# 2-nand-gate-latching-circuit.net
KiCad netlist of a schematic drawn in EAGLE
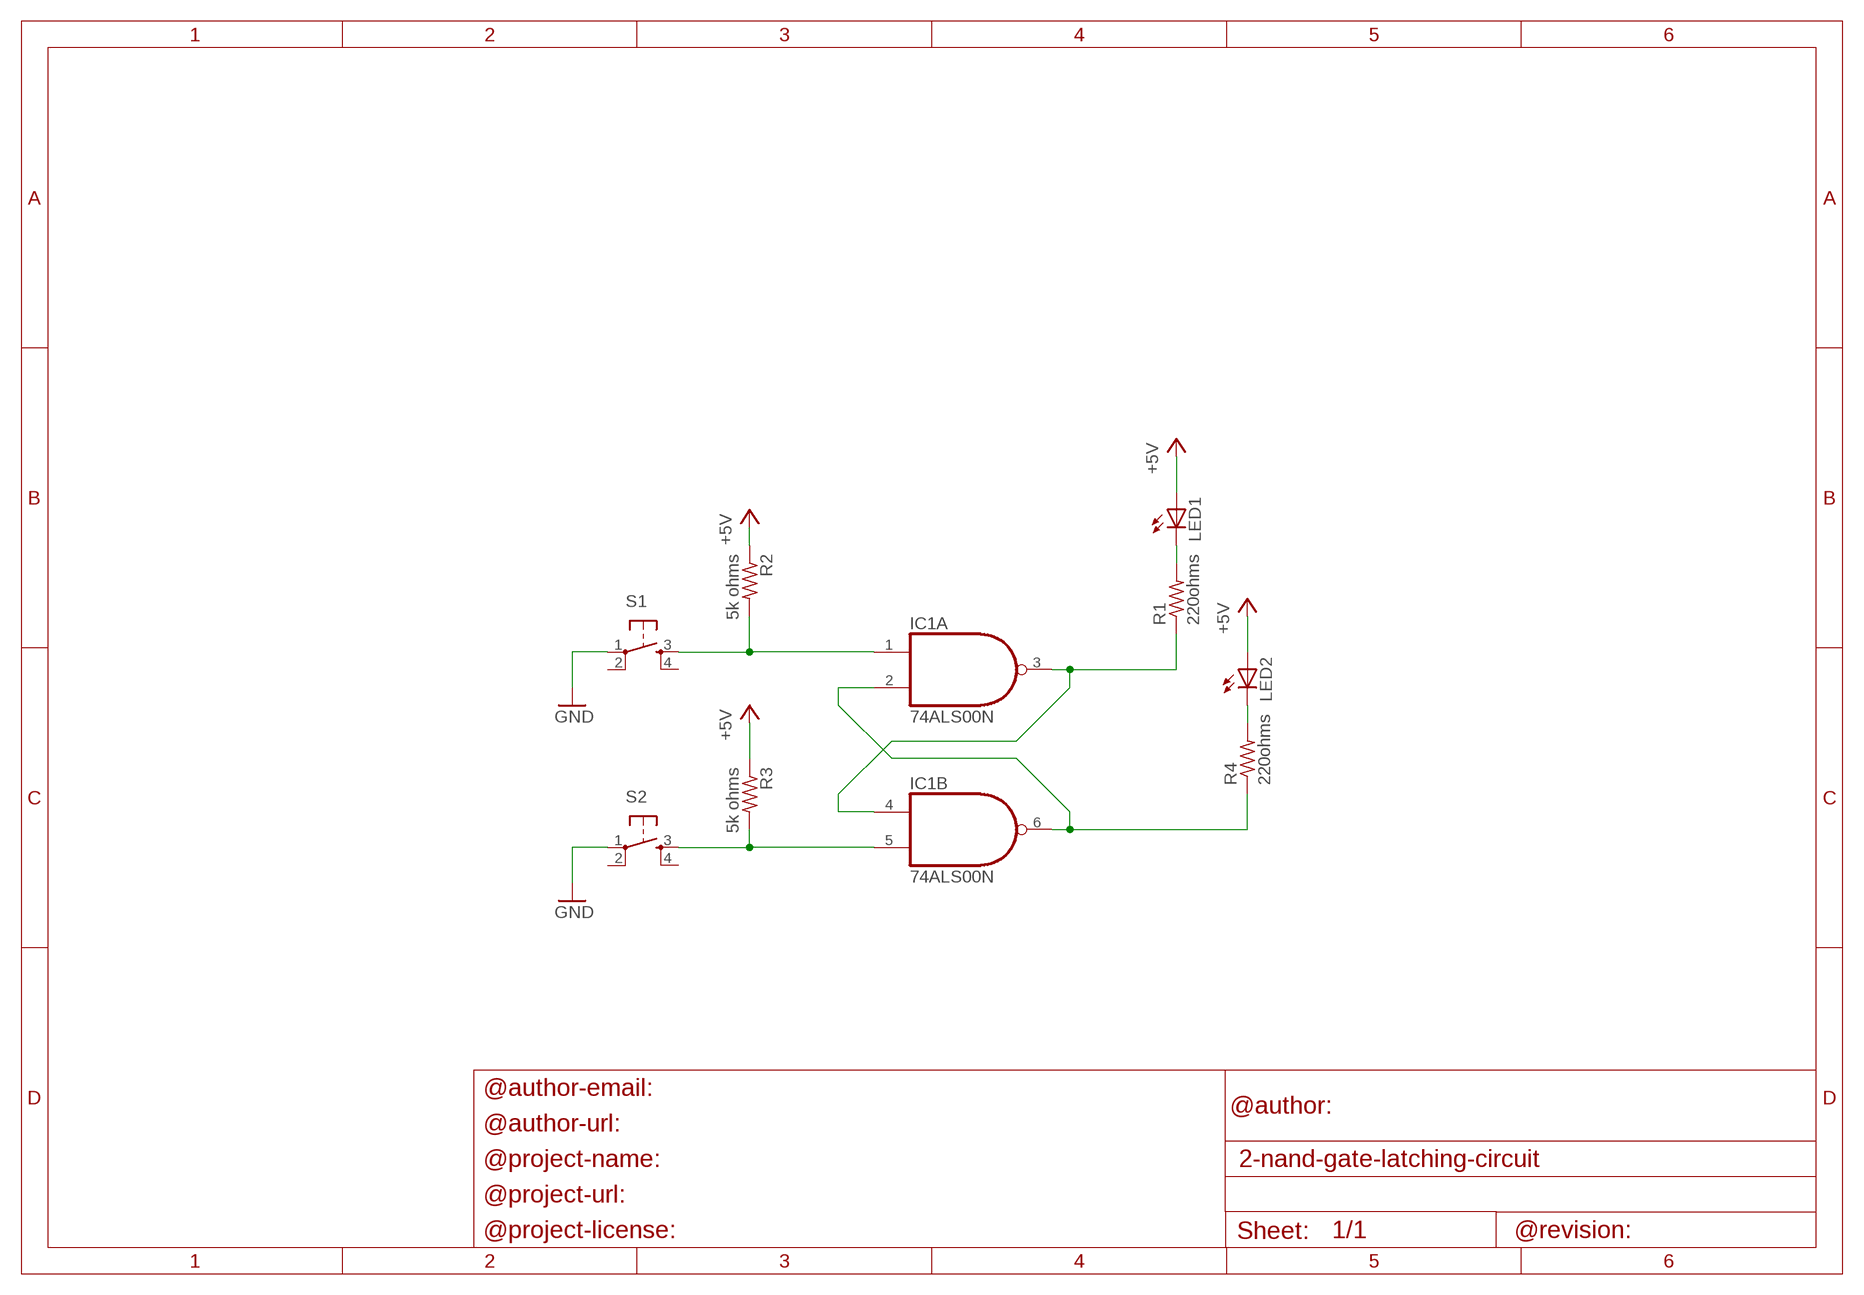
[diagram p0: schematic, sheet 1]

(export (version "E")
  (design (tool "Eeschema 10.0.6"))
  (components
    (comp (ref "IC1")
      (value "74ALS00N")
      (footprint "eagle-import:DIL14")
      (libsource (lib "eagle-import") (part "7400NALS"))
    )
    (comp (ref "LED1")
      (value "LED5MM")
      (footprint "eagle-import:LED5MM")
      (libsource (lib "eagle-import") (part "LED5MM"))
    )
    (comp (ref "LED2")
      (value "LED5MM")
      (footprint "eagle-import:LED5MM")
      (libsource (lib "eagle-import") (part "LED5MM"))
    )
    (comp (ref "R1")
      (value "220ohms")
      (footprint "eagle-import:0204_7")
      (libsource (lib "eagle-import") (part "R-US_0204/7"))
    )
    (comp (ref "R2")
      (value "5k ohms")
      (footprint "eagle-import:0204_7")
      (libsource (lib "eagle-import") (part "R-US_0204/7"))
    )
    (comp (ref "R3")
      (value "5k ohms")
      (footprint "eagle-import:0204_7")
      (libsource (lib "eagle-import") (part "R-US_0204/7"))
    )
    (comp (ref "R4")
      (value "220ohms")
      (footprint "eagle-import:0204_7")
      (libsource (lib "eagle-import") (part "R-US_0204/7"))
    )
    (comp (ref "S1")
      (value "TAC_SWITCHPTH")
      (footprint "eagle-import:TACTILE-PTH")
      (libsource (lib "eagle-import") (part "TAC_SWITCHPTH"))
    )
    (comp (ref "S2")
      (value "TAC_SWITCHPTH")
      (footprint "eagle-import:TACTILE-PTH")
      (libsource (lib "eagle-import") (part "TAC_SWITCHPTH"))
    )
  )
  (nets
    (net (code "1") (name "+5V") (class "Default")
      (node (ref "LED1") (pin "A") (pinfunction "A_A") (pintype "passive"))
      (node (ref "LED2") (pin "A") (pinfunction "A_A") (pintype "passive"))
      (node (ref "R2") (pin "1") (pinfunction "1_1") (pintype "passive"))
      (node (ref "R3") (pin "1") (pinfunction "1_1") (pintype "passive"))
    )
    (net (code "2") (name "GND") (class "Default")
      (node (ref "S1") (pin "1") (pinfunction "1_1") (pintype "passive"))
      (node (ref "S2") (pin "1") (pinfunction "1_1") (pintype "passive"))
    )
    (net (code "3") (name "Net-(IC1A-I0)") (class "Default")
      (node (ref "IC1") (pin "1") (pinfunction "I0_1") (pintype "input"))
      (node (ref "R2") (pin "2") (pinfunction "2_2") (pintype "passive"))
      (node (ref "S1") (pin "3") (pinfunction "3_3") (pintype "passive"))
    )
    (net (code "4") (name "Net-(IC1A-I1)") (class "Default")
      (node (ref "IC1") (pin "2") (pinfunction "I1_2") (pintype "input"))
      (node (ref "IC1") (pin "6") (pinfunction "O_6") (pintype "output"))
      (node (ref "R4") (pin "1") (pinfunction "1_1") (pintype "passive"))
    )
    (net (code "5") (name "Net-(IC1A-O)") (class "Default")
      (node (ref "IC1") (pin "3") (pinfunction "O_3") (pintype "output"))
      (node (ref "IC1") (pin "4") (pinfunction "I0_4") (pintype "input"))
      (node (ref "R1") (pin "1") (pinfunction "1_1") (pintype "passive"))
    )
    (net (code "6") (name "Net-(IC1B-I1)") (class "Default")
      (node (ref "IC1") (pin "5") (pinfunction "I1_5") (pintype "input"))
      (node (ref "R3") (pin "2") (pinfunction "2_2") (pintype "passive"))
      (node (ref "S2") (pin "3") (pinfunction "3_3") (pintype "passive"))
    )
    (net (code "7") (name "Net-(LED1-C)") (class "Default")
      (node (ref "LED1") (pin "K") (pinfunction "C_K") (pintype "passive"))
      (node (ref "R1") (pin "2") (pinfunction "2_2") (pintype "passive"))
    )
    (net (code "8") (name "Net-(LED2-C)") (class "Default")
      (node (ref "LED2") (pin "K") (pinfunction "C_K") (pintype "passive"))
      (node (ref "R4") (pin "2") (pinfunction "2_2") (pintype "passive"))
    )
    (net (code "9") (name "unconnected-(S1-Pad2)") (class "Default")
      (node (ref "S1") (pin "2") (pinfunction "2_2") (pintype "passive"))
    )
    (net (code "10") (name "unconnected-(S1-Pad4)") (class "Default")
      (node (ref "S1") (pin "4") (pinfunction "4_4") (pintype "passive"))
    )
    (net (code "11") (name "unconnected-(S2-Pad2)") (class "Default")
      (node (ref "S2") (pin "2") (pinfunction "2_2") (pintype "passive"))
    )
    (net (code "12") (name "unconnected-(S2-Pad4)") (class "Default")
      (node (ref "S2") (pin "4") (pinfunction "4_4") (pintype "passive"))
    )
  )
)
